# COEXPIX_connectors_schematics.net
KiCad netlist of a schematic drawn in Altium Designer
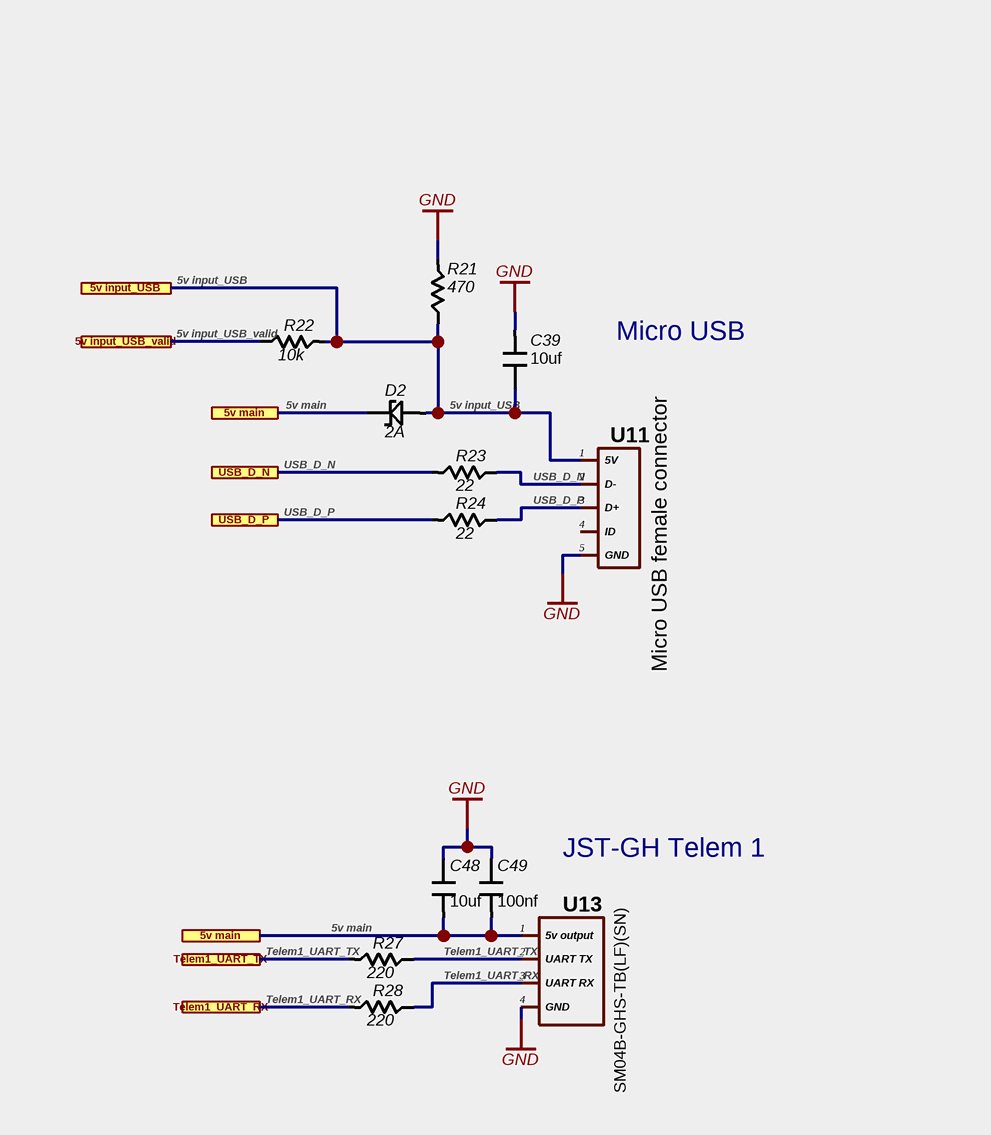
[diagram p0: COEXPIX connectors schematics.SchDoc, top left]
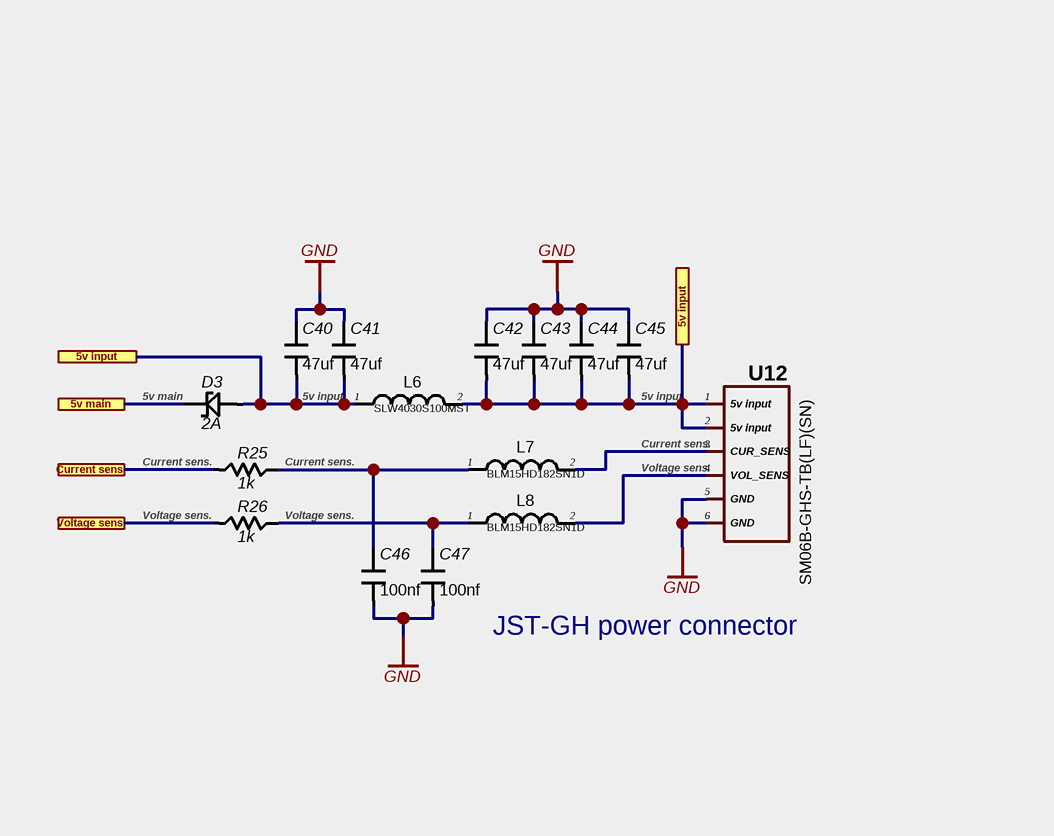
[diagram p1: COEXPIX connectors schematics.SchDoc, top right]
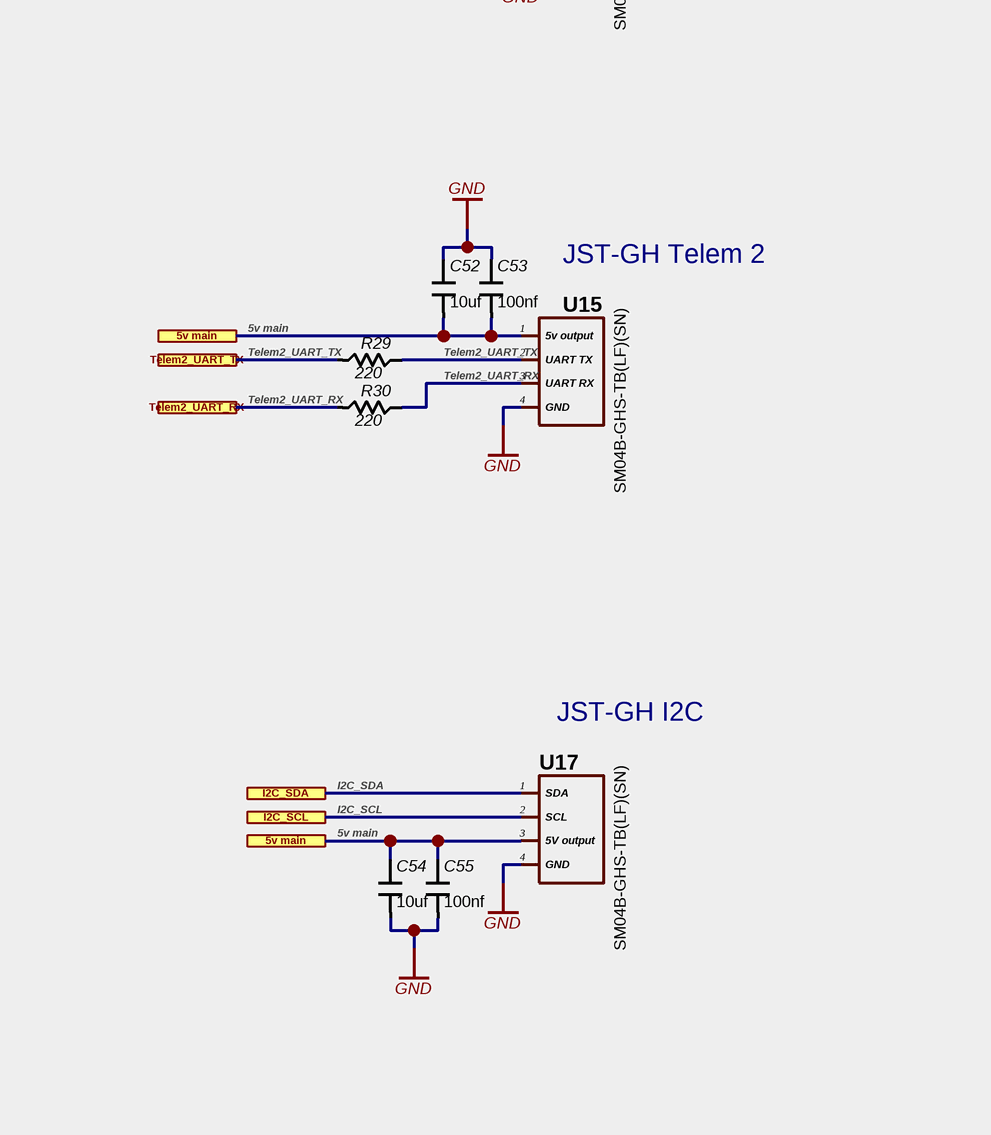
[diagram p2: COEXPIX connectors schematics.SchDoc, bottom left]
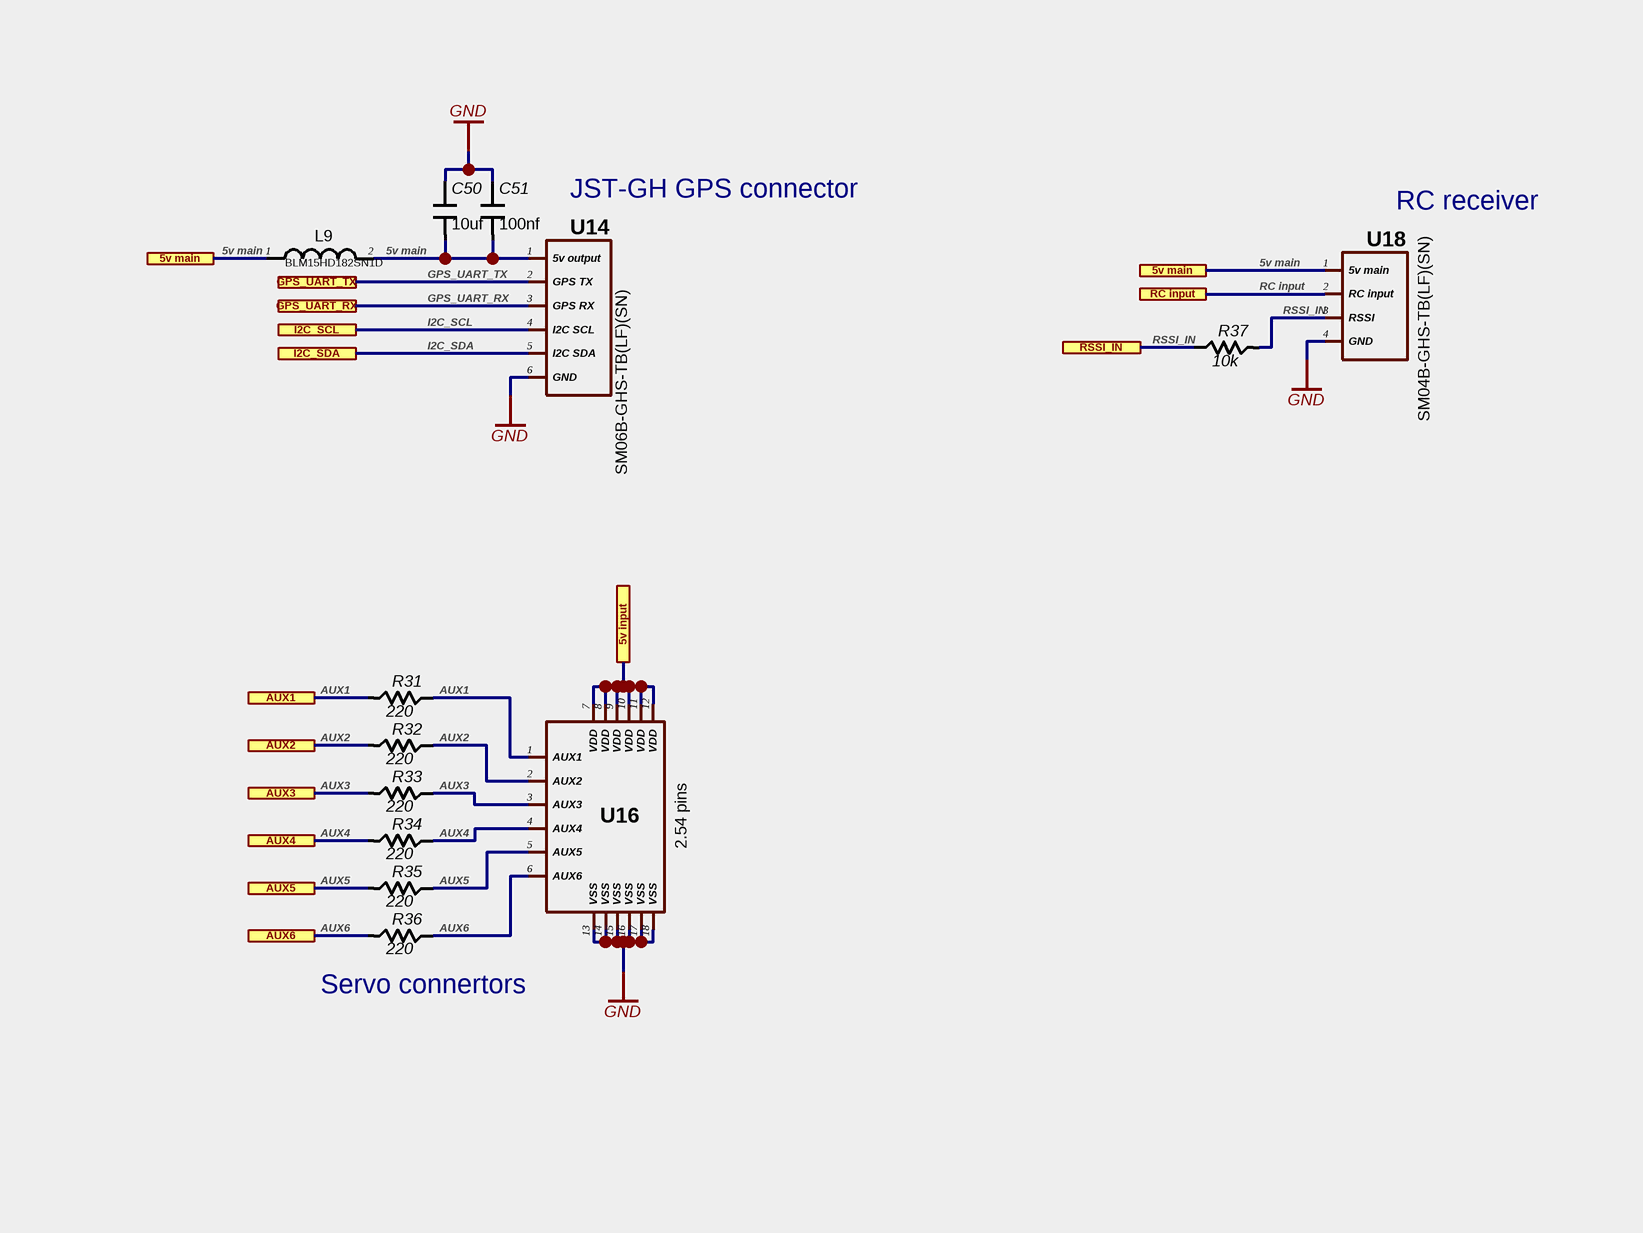
[diagram p3: COEXPIX connectors schematics.SchDoc, bottom right]

(export (version "E")
  (design (tool "Eeschema 10.0.6"))
  (components
    (comp (ref "C39")
      (value "10uf")
      (footprint "Capasitor 0402")
      (description "Multilayer Ceramic Capacitors MLCC - SMD/SMT 10uF 6.3V 0402")
      (fields (field (name "PART NUMBER") "JMK105CBJ106MV-F") (field (name "MANUFACTURER") "Taiyo Yuden"))
      (libsource (lib "Schematic symbols library") (part "Capacitor MLCC"))
    )
    (comp (ref "C40")
      (value "47uf")
      (footprint "Capasitor 0603")
      (description "Multilayer Ceramic Capacitors MLCC - SMD/SMT 47uF 6.3V 0603")
      (fields (field (name "PART NUMBER") "GRM188R60J476ME15D") (field (name "MANUFACTURER") "Murata"))
      (libsource (lib "Schematic symbols library") (part "Capacitor MLCC"))
    )
    (comp (ref "C41")
      (value "47uf")
      (footprint "Capasitor 0603")
      (description "Multilayer Ceramic Capacitors MLCC - SMD/SMT 47uF 6.3V 0603")
      (fields (field (name "PART NUMBER") "GRM188R60J476ME15D") (field (name "MANUFACTURER") "Murata"))
      (libsource (lib "Schematic symbols library") (part "Capacitor MLCC"))
    )
    (comp (ref "C42")
      (value "47uf")
      (footprint "Capasitor 0603")
      (description "Multilayer Ceramic Capacitors MLCC - SMD/SMT 47uF 6.3V 0603")
      (fields (field (name "PART NUMBER") "GRM188R60J476ME15D") (field (name "MANUFACTURER") "Murata"))
      (libsource (lib "Schematic symbols library") (part "Capacitor MLCC"))
    )
    (comp (ref "C43")
      (value "47uf")
      (footprint "Capasitor 0603")
      (description "Multilayer Ceramic Capacitors MLCC - SMD/SMT 47uF 6.3V 0603")
      (fields (field (name "PART NUMBER") "GRM188R60J476ME15D") (field (name "MANUFACTURER") "Murata"))
      (libsource (lib "Schematic symbols library") (part "Capacitor MLCC"))
    )
    (comp (ref "C44")
      (value "47uf")
      (footprint "Capasitor 0603")
      (description "Multilayer Ceramic Capacitors MLCC - SMD/SMT 47uF 6.3V 0603")
      (fields (field (name "PART NUMBER") "GRM188R60J476ME15D") (field (name "MANUFACTURER") "Murata"))
      (libsource (lib "Schematic symbols library") (part "Capacitor MLCC"))
    )
    (comp (ref "C45")
      (value "47uf")
      (footprint "Capasitor 0603")
      (description "Multilayer Ceramic Capacitors MLCC - SMD/SMT 47uF 6.3V 0603")
      (fields (field (name "PART NUMBER") "GRM188R60J476ME15D") (field (name "MANUFACTURER") "Murata"))
      (libsource (lib "Schematic symbols library") (part "Capacitor MLCC"))
    )
    (comp (ref "C46")
      (value "100nf")
      (footprint "Capasitor 0402")
      (description "Multilayer Ceramic Capacitors MLCC - SMD/SMT 100nF 16V 0402")
      (fields (field (name "PART NUMBER") "CC0402KRX7R7BB104") (field (name "MANUFACTURER") "YAGEO"))
      (libsource (lib "Schematic symbols library") (part "Capacitor MLCC"))
    )
    (comp (ref "C47")
      (value "100nf")
      (footprint "Capasitor 0402")
      (description "Multilayer Ceramic Capacitors MLCC - SMD/SMT 100nF 16V 0402")
      (fields (field (name "PART NUMBER") "CC0402KRX7R7BB104") (field (name "MANUFACTURER") "YAGEO"))
      (libsource (lib "Schematic symbols library") (part "Capacitor MLCC"))
    )
    (comp (ref "C48")
      (value "10uf")
      (footprint "Capasitor 0402")
      (description "Multilayer Ceramic Capacitors MLCC - SMD/SMT 10uF 6.3V 0402")
      (fields (field (name "PART NUMBER") "JMK105CBJ106MV-F") (field (name "MANUFACTURER") "Taiyo Yuden"))
      (libsource (lib "Schematic symbols library") (part "Capacitor MLCC"))
    )
    (comp (ref "C49")
      (value "100nf")
      (footprint "Capasitor 0402")
      (description "Multilayer Ceramic Capacitors MLCC - SMD/SMT 100nF 16V 0402")
      (fields (field (name "PART NUMBER") "CC0402KRX7R7BB104") (field (name "MANUFACTURER") "YAGEO"))
      (libsource (lib "Schematic symbols library") (part "Capacitor MLCC"))
    )
    (comp (ref "C50")
      (value "10uf")
      (footprint "Capasitor 0402")
      (description "Multilayer Ceramic Capacitors MLCC - SMD/SMT 10uF 6.3V 0402")
      (fields (field (name "PART NUMBER") "JMK105CBJ106MV-F") (field (name "MANUFACTURER") "Taiyo Yuden"))
      (libsource (lib "Schematic symbols library") (part "Capacitor MLCC"))
    )
    (comp (ref "C51")
      (value "100nf")
      (footprint "Capasitor 0402")
      (description "Multilayer Ceramic Capacitors MLCC - SMD/SMT 100nF 16V 0402")
      (fields (field (name "PART NUMBER") "CC0402KRX7R7BB104") (field (name "MANUFACTURER") "YAGEO"))
      (libsource (lib "Schematic symbols library") (part "Capacitor MLCC"))
    )
    (comp (ref "C52")
      (value "10uf")
      (footprint "Capasitor 0402")
      (description "Multilayer Ceramic Capacitors MLCC - SMD/SMT 10uF 6.3V 0402")
      (fields (field (name "PART NUMBER") "JMK105CBJ106MV-F") (field (name "MANUFACTURER") "Taiyo Yuden"))
      (libsource (lib "Schematic symbols library") (part "Capacitor MLCC"))
    )
    (comp (ref "C53")
      (value "100nf")
      (footprint "Capasitor 0402")
      (description "Multilayer Ceramic Capacitors MLCC - SMD/SMT 100nF 16V 0402")
      (fields (field (name "PART NUMBER") "CC0402KRX7R7BB104") (field (name "MANUFACTURER") "YAGEO"))
      (libsource (lib "Schematic symbols library") (part "Capacitor MLCC"))
    )
    (comp (ref "C54")
      (value "10uf")
      (footprint "Capasitor 0402")
      (description "Multilayer Ceramic Capacitors MLCC - SMD/SMT 10uF 6.3V 0402")
      (fields (field (name "PART NUMBER") "JMK105CBJ106MV-F") (field (name "MANUFACTURER") "Taiyo Yuden"))
      (libsource (lib "Schematic symbols library") (part "Capacitor MLCC"))
    )
    (comp (ref "C55")
      (value "100nf")
      (footprint "Capasitor 0402")
      (description "Multilayer Ceramic Capacitors MLCC - SMD/SMT 100nF 16V 0402")
      (fields (field (name "PART NUMBER") "CC0402KRX7R7BB104") (field (name "MANUFACTURER") "YAGEO"))
      (libsource (lib "Schematic symbols library") (part "Capacitor MLCC"))
    )
    (comp (ref "D2")
      (value "2A")
      (footprint "SOD-323F")
      (description "Schottky Barrier Diodes (SBD) SOD-323F")
      (fields (field (name "PART NUMBER") "SGP0230SD") (field (name "MANUFACTURER") "Suzhou Good-Ark Elec"))
      (libsource (lib "Schematic symbols library") (part "Schottky barrier diode"))
    )
    (comp (ref "D3")
      (value "2A")
      (footprint "SOD-323F")
      (description "Schottky Barrier Diodes (SBD) SOD-323F")
      (fields (field (name "PART NUMBER") "SGP0230SD") (field (name "MANUFACTURER") "Suzhou Good-Ark Elec"))
      (libsource (lib "Schematic symbols library") (part "Schottky barrier diode"))
    )
    (comp (ref "L6")
      (value "SLW4030S100MST")
      (footprint "Inductor 4030")
      (description "Power Inductors 10uH ±20% 1.5A SMD,4x4x3mm")
      (fields (field (name "MANUFACTURER") "Sunltech Tech"))
      (libsource (lib "Schematic symbols library") (part "FB / Inductor"))
    )
    (comp (ref "L7")
      (value "BLM15HD182SN1D")
      (footprint "Ferrite bead 0402")
      (description "Beads 0402")
      (fields (field (name "MANUFACTURER") "Murata Electronics"))
      (libsource (lib "Schematic symbols library") (part "FB / Inductor"))
    )
    (comp (ref "L8")
      (value "BLM15HD182SN1D")
      (footprint "Ferrite bead 0402")
      (description "Beads 0402")
      (fields (field (name "MANUFACTURER") "Murata Electronics"))
      (libsource (lib "Schematic symbols library") (part "FB / Inductor"))
    )
    (comp (ref "L9")
      (value "BLM15HD182SN1D")
      (footprint "Ferrite bead 0402")
      (description "Beads 0402")
      (fields (field (name "MANUFACTURER") "Murata Electronics"))
      (libsource (lib "Schematic symbols library") (part "FB / Inductor"))
    )
    (comp (ref "R21")
      (value "470")
      (footprint "Resistor 0402")
      (description "Chip Resistor - Surface Mount 470Ohms ±1% 1/16W 0402")
      (fields (field (name "PART NUMBER") "RC0402FR-07470RL") (field (name "MANUFACTURER") "YAGEO"))
      (libsource (lib "Schematic symbols library") (part "Resistor"))
    )
    (comp (ref "R22")
      (value "10k")
      (footprint "Resistor 0402")
      (description "Chip Resistor - Surface Mount 10KOhms ±1% 1/16W 0402")
      (fields (field (name "PART NUMBER") "RC0402FR-0710KL") (field (name "MANUFACTURER") "YAGEO"))
      (libsource (lib "Schematic symbols library") (part "Resistor"))
    )
    (comp (ref "R23")
      (value "22")
      (footprint "Resistor 0402")
      (description "Chip Resistor - Surface Mount 22Ohms ±1% 1/16W 0402")
      (fields (field (name "PART NUMBER") "RC0402FR-0722RL") (field (name "MANUFACTURER") "YAGEO"))
      (libsource (lib "Schematic symbols library") (part "Resistor"))
    )
    (comp (ref "R24")
      (value "22")
      (footprint "Resistor 0402")
      (description "Chip Resistor - Surface Mount 22Ohms ±1% 1/16W 0402")
      (fields (field (name "PART NUMBER") "RC0402FR-0722RL") (field (name "MANUFACTURER") "YAGEO"))
      (libsource (lib "Schematic symbols library") (part "Resistor"))
    )
    (comp (ref "R25")
      (value "1k")
      (footprint "Resistor 0402")
      (description "Chip Resistor - Surface Mount 1KOhms ±1% 1/16W 0402")
      (fields (field (name "PART NUMBER") "RC0402FR-071KL") (field (name "MANUFACTURER") "YAGEO"))
      (libsource (lib "Schematic symbols library") (part "Resistor"))
    )
    (comp (ref "R26")
      (value "1k")
      (footprint "Resistor 0402")
      (description "Chip Resistor - Surface Mount 1KOhms ±1% 1/16W 0402")
      (fields (field (name "PART NUMBER") "RC0402FR-071KL") (field (name "MANUFACTURER") "YAGEO"))
      (libsource (lib "Schematic symbols library") (part "Resistor"))
    )
    (comp (ref "R27")
      (value "220")
      (footprint "Resistor 0402")
      (description "Chip Resistor - Surface Mount 220Ohms ±1% 1/16W 040")
      (fields (field (name "PART NUMBER") "0402WGF2200TCE") (field (name "MANUFACTURER") "Uniroyal Elec"))
      (libsource (lib "Schematic symbols library") (part "Resistor"))
    )
    (comp (ref "R28")
      (value "220")
      (footprint "Resistor 0402")
      (description "Chip Resistor - Surface Mount 220Ohms ±1% 1/16W 040")
      (fields (field (name "PART NUMBER") "0402WGF2200TCE") (field (name "MANUFACTURER") "Uniroyal Elec"))
      (libsource (lib "Schematic symbols library") (part "Resistor"))
    )
    (comp (ref "R29")
      (value "220")
      (footprint "Resistor 0402")
      (description "Chip Resistor - Surface Mount 220Ohms ±1% 1/16W 040")
      (fields (field (name "PART NUMBER") "0402WGF2200TCE") (field (name "MANUFACTURER") "Uniroyal Elec"))
      (libsource (lib "Schematic symbols library") (part "Resistor"))
    )
    (comp (ref "R30")
      (value "220")
      (footprint "Resistor 0402")
      (description "Chip Resistor - Surface Mount 220Ohms ±1% 1/16W 040")
      (fields (field (name "PART NUMBER") "0402WGF2200TCE") (field (name "MANUFACTURER") "Uniroyal Elec"))
      (libsource (lib "Schematic symbols library") (part "Resistor"))
    )
    (comp (ref "R31")
      (value "220")
      (footprint "Resistor 0402")
      (description "Chip Resistor - Surface Mount 220Ohms ±1% 1/16W 040")
      (fields (field (name "PART NUMBER") "0402WGF2200TCE") (field (name "MANUFACTURER") "Uniroyal Elec"))
      (libsource (lib "Schematic symbols library") (part "Resistor"))
    )
    (comp (ref "R32")
      (value "220")
      (footprint "Resistor 0402")
      (description "Chip Resistor - Surface Mount 220Ohms ±1% 1/16W 040")
      (fields (field (name "PART NUMBER") "0402WGF2200TCE") (field (name "MANUFACTURER") "Uniroyal Elec"))
      (libsource (lib "Schematic symbols library") (part "Resistor"))
    )
    (comp (ref "R33")
      (value "220")
      (footprint "Resistor 0402")
      (description "Chip Resistor - Surface Mount 220Ohms ±1% 1/16W 040")
      (fields (field (name "PART NUMBER") "0402WGF2200TCE") (field (name "MANUFACTURER") "Uniroyal Elec"))
      (libsource (lib "Schematic symbols library") (part "Resistor"))
    )
    (comp (ref "R34")
      (value "220")
      (footprint "Resistor 0402")
      (description "Chip Resistor - Surface Mount 220Ohms ±1% 1/16W 040")
      (fields (field (name "PART NUMBER") "0402WGF2200TCE") (field (name "MANUFACTURER") "Uniroyal Elec"))
      (libsource (lib "Schematic symbols library") (part "Resistor"))
    )
    (comp (ref "R35")
      (value "220")
      (footprint "Resistor 0402")
      (description "Chip Resistor - Surface Mount 220Ohms ±1% 1/16W 040")
      (fields (field (name "PART NUMBER") "0402WGF2200TCE") (field (name "MANUFACTURER") "Uniroyal Elec"))
      (libsource (lib "Schematic symbols library") (part "Resistor"))
    )
    (comp (ref "R36")
      (value "220")
      (footprint "Resistor 0402")
      (description "Chip Resistor - Surface Mount 220Ohms ±1% 1/16W 040")
      (fields (field (name "PART NUMBER") "0402WGF2200TCE") (field (name "MANUFACTURER") "Uniroyal Elec"))
      (libsource (lib "Schematic symbols library") (part "Resistor"))
    )
    (comp (ref "R37")
      (value "10k")
      (footprint "Resistor 0402")
      (description "Chip Resistor - Surface Mount 10KOhms ±1% 1/16W 0402")
      (fields (field (name "PART NUMBER") "RC0402FR-0710KL") (field (name "MANUFACTURER") "YAGEO"))
      (libsource (lib "Schematic symbols library") (part "Resistor"))
    )
    (comp (ref "U11")
      (value "Micro USB female connector")
      (footprint "Micro USB")
      (libsource (lib "Schematic symbols library") (part "Micro USB"))
    )
    (comp (ref "U12")
      (value "SM06B-GHS-TB(LF)(SN)")
      (footprint "JST-GH 6 PIN")
      (description "Wire To Board / Wire To Wire Connector SMD")
      (fields (field (name "MANUFACTURER") "JST Sales America"))
      (libsource (lib "Schematic symbols library") (part "JST-GH 6"))
    )
    (comp (ref "U13")
      (value "SM04B-GHS-TB(LF)(SN)")
      (footprint "JST-GH 4 pin")
      (description "Wire To Board / Wire To Wire Connector socket P=1.25mm")
      (fields (field (name "MANUFACTURER") "JST Sales America"))
      (libsource (lib "Schematic symbols library") (part "JST-GH 4"))
    )
    (comp (ref "U14")
      (value "SM06B-GHS-TB(LF)(SN)")
      (footprint "JST-GH 6 PIN")
      (description "Wire To Board / Wire To Wire Connector SMD")
      (fields (field (name "MANUFACTURER") "JST Sales America"))
      (libsource (lib "Schematic symbols library") (part "JST-GH 6"))
    )
    (comp (ref "U15")
      (value "SM04B-GHS-TB(LF)(SN)")
      (footprint "JST-GH 4 pin")
      (description "Wire To Board / Wire To Wire Connector socket P=1.25mm")
      (fields (field (name "MANUFACTURER") "JST Sales America"))
      (libsource (lib "Schematic symbols library") (part "JST-GH 4"))
    )
    (comp (ref "U16")
      (value "2.54 pins")
      (footprint "3x6 PX4 servo array")
      (fields (field (name "PART NUMBER") "2.54 pins array"))
      (libsource (lib "Schematic symbols library") (part "3x6 dupont pins"))
    )
    (comp (ref "U17")
      (value "SM04B-GHS-TB(LF)(SN)")
      (footprint "JST-GH 4 pin")
      (description "Wire To Board / Wire To Wire Connector socket P=1.25mm")
      (fields (field (name "MANUFACTURER") "JST Sales America"))
      (libsource (lib "Schematic symbols library") (part "JST-GH 4"))
    )
    (comp (ref "U18")
      (value "SM04B-GHS-TB(LF)(SN)")
      (footprint "JST-GH 4 pin")
      (description "Wire To Board / Wire To Wire Connector socket P=1.25mm")
      (fields (field (name "MANUFACTURER") "JST Sales America"))
      (libsource (lib "Schematic symbols library") (part "JST-GH 4"))
    )
  )
  (nets
    (net (code "1") (name "/5v input") (class "Default")
      (node (ref "C40") (pin "2") (pinfunction "2_2") (pintype "passive"))
      (node (ref "C41") (pin "2") (pinfunction "2_2") (pintype "passive"))
      (node (ref "C42") (pin "2") (pinfunction "2_2") (pintype "passive"))
      (node (ref "C43") (pin "2") (pinfunction "2_2") (pintype "passive"))
      (node (ref "C44") (pin "2") (pinfunction "2_2") (pintype "passive"))
      (node (ref "C45") (pin "2") (pinfunction "2_2") (pintype "passive"))
      (node (ref "D3") (pin "2") (pinfunction "2_2") (pintype "passive"))
      (node (ref "L6") (pin "1") (pintype "power_in"))
      (node (ref "L6") (pin "2") (pintype "power_in"))
      (node (ref "U12") (pin "1") (pinfunction "5v_output_1") (pintype "power_in"))
      (node (ref "U12") (pin "2") (pinfunction "GPS_TX_2") (pintype "power_in"))
      (node (ref "U16") (pin "10") (pinfunction "VDD_10") (pintype "power_in"))
      (node (ref "U16") (pin "11") (pinfunction "VDD_11") (pintype "power_in"))
      (node (ref "U16") (pin "12") (pinfunction "VDD_12") (pintype "power_in"))
      (node (ref "U16") (pin "7") (pinfunction "VDD_7") (pintype "power_in"))
      (node (ref "U16") (pin "8") (pinfunction "VDD_8") (pintype "power_in"))
      (node (ref "U16") (pin "9") (pinfunction "VDD_9") (pintype "power_in"))
    )
    (net (code "2") (name "/5v input_USB") (class "Default")
      (node (ref "C39") (pin "1") (pinfunction "1_1") (pintype "passive"))
      (node (ref "D2") (pin "2") (pinfunction "2_2") (pintype "passive"))
      (node (ref "R21") (pin "1") (pinfunction "1_1") (pintype "passive"))
      (node (ref "R22") (pin "2") (pinfunction "2_2") (pintype "passive"))
      (node (ref "U11") (pin "1") (pinfunction "5V_1") (pintype "power_in"))
    )
    (net (code "3") (name "/5v input_USB_valid") (class "Default")
      (node (ref "R22") (pin "1") (pinfunction "1_1") (pintype "passive"))
    )
    (net (code "4") (name "/5v main") (class "Default")
      (node (ref "C48") (pin "2") (pinfunction "2_2") (pintype "passive"))
      (node (ref "C49") (pin "2") (pinfunction "2_2") (pintype "passive"))
      (node (ref "C50") (pin "2") (pinfunction "2_2") (pintype "passive"))
      (node (ref "C51") (pin "2") (pinfunction "2_2") (pintype "passive"))
      (node (ref "C52") (pin "2") (pinfunction "2_2") (pintype "passive"))
      (node (ref "C53") (pin "2") (pinfunction "2_2") (pintype "passive"))
      (node (ref "C54") (pin "1") (pinfunction "1_1") (pintype "passive"))
      (node (ref "C55") (pin "1") (pinfunction "1_1") (pintype "passive"))
      (node (ref "D2") (pin "1") (pinfunction "1_1") (pintype "passive"))
      (node (ref "D3") (pin "1") (pinfunction "1_1") (pintype "passive"))
      (node (ref "L9") (pin "1") (pintype "power_in"))
      (node (ref "L9") (pin "2") (pintype "power_in"))
      (node (ref "U13") (pin "1") (pinfunction "5v_output_1") (pintype "power_in"))
      (node (ref "U14") (pin "1") (pinfunction "5v_output_1") (pintype "power_in"))
      (node (ref "U15") (pin "1") (pinfunction "5v_output_1") (pintype "power_in"))
      (node (ref "U17") (pin "3") (pinfunction "UART_RX_3") (pintype "power_in"))
      (node (ref "U18") (pin "1") (pinfunction "5v_output_1") (pintype "power_in"))
    )
    (net (code "5") (name "/AUX1") (class "Default")
      (node (ref "R31") (pin "1") (pinfunction "1_1") (pintype "passive"))
      (node (ref "R31") (pin "2") (pinfunction "2_2") (pintype "passive"))
      (node (ref "U16") (pin "1") (pinfunction "AUX1_1") (pintype "power_in"))
    )
    (net (code "6") (name "/AUX2") (class "Default")
      (node (ref "R32") (pin "1") (pinfunction "1_1") (pintype "passive"))
      (node (ref "R32") (pin "2") (pinfunction "2_2") (pintype "passive"))
      (node (ref "U16") (pin "2") (pinfunction "AUX2_2") (pintype "power_in"))
    )
    (net (code "7") (name "/AUX3") (class "Default")
      (node (ref "R33") (pin "1") (pinfunction "1_1") (pintype "passive"))
      (node (ref "R33") (pin "2") (pinfunction "2_2") (pintype "passive"))
      (node (ref "U16") (pin "3") (pinfunction "AUX3_3") (pintype "power_in"))
    )
    (net (code "8") (name "/AUX4") (class "Default")
      (node (ref "R34") (pin "1") (pinfunction "1_1") (pintype "passive"))
      (node (ref "R34") (pin "2") (pinfunction "2_2") (pintype "passive"))
      (node (ref "U16") (pin "4") (pinfunction "AUX4_4") (pintype "power_in"))
    )
    (net (code "9") (name "/AUX5") (class "Default")
      (node (ref "R35") (pin "1") (pinfunction "1_1") (pintype "passive"))
      (node (ref "R35") (pin "2") (pinfunction "2_2") (pintype "passive"))
      (node (ref "U16") (pin "5") (pinfunction "AUX5_5") (pintype "power_in"))
    )
    (net (code "10") (name "/AUX6") (class "Default")
      (node (ref "R36") (pin "1") (pinfunction "1_1") (pintype "passive"))
      (node (ref "R36") (pin "2") (pinfunction "2_2") (pintype "passive"))
      (node (ref "U16") (pin "6") (pinfunction "AUX6_6") (pintype "power_in"))
    )
    (net (code "11") (name "/Current sens.") (class "Default")
      (node (ref "C46") (pin "1") (pinfunction "1_1") (pintype "passive"))
      (node (ref "L7") (pin "1") (pintype "power_in"))
      (node (ref "L7") (pin "2") (pintype "power_in"))
      (node (ref "R25") (pin "1") (pinfunction "1_1") (pintype "passive"))
      (node (ref "R25") (pin "2") (pinfunction "2_2") (pintype "passive"))
      (node (ref "U12") (pin "3") (pinfunction "GPS_RX_3") (pintype "power_in"))
    )
    (net (code "12") (name "/GPS_UART_RX") (class "Default")
      (node (ref "U14") (pin "3") (pinfunction "GPS_RX_3") (pintype "power_in"))
    )
    (net (code "13") (name "/GPS_UART_TX") (class "Default")
      (node (ref "U14") (pin "2") (pinfunction "GPS_TX_2") (pintype "power_in"))
    )
    (net (code "14") (name "/I2C_SCL") (class "Default")
      (node (ref "U14") (pin "4") (pinfunction "I2C_SCL_4") (pintype "power_in"))
      (node (ref "U17") (pin "2") (pinfunction "UART_TX_2") (pintype "power_in"))
    )
    (net (code "15") (name "/I2C_SDA") (class "Default")
      (node (ref "U14") (pin "5") (pinfunction "I2C_SDA_5") (pintype "power_in"))
      (node (ref "U17") (pin "1") (pinfunction "5v_output_1") (pintype "power_in"))
    )
    (net (code "16") (name "/RC input") (class "Default")
      (node (ref "U18") (pin "2") (pinfunction "UART_TX_2") (pintype "power_in"))
    )
    (net (code "17") (name "/RSSI_IN") (class "Default")
      (node (ref "R37") (pin "1") (pinfunction "1_1") (pintype "passive"))
      (node (ref "R37") (pin "2") (pinfunction "2_2") (pintype "passive"))
      (node (ref "U18") (pin "3") (pinfunction "UART_RX_3") (pintype "power_in"))
    )
    (net (code "18") (name "/Telem1_UART_RX") (class "Default")
      (node (ref "R28") (pin "1") (pinfunction "1_1") (pintype "passive"))
      (node (ref "R28") (pin "2") (pinfunction "2_2") (pintype "passive"))
      (node (ref "U13") (pin "3") (pinfunction "UART_RX_3") (pintype "power_in"))
    )
    (net (code "19") (name "/Telem1_UART_TX") (class "Default")
      (node (ref "R27") (pin "1") (pinfunction "1_1") (pintype "passive"))
      (node (ref "R27") (pin "2") (pinfunction "2_2") (pintype "passive"))
      (node (ref "U13") (pin "2") (pinfunction "UART_TX_2") (pintype "power_in"))
    )
    (net (code "20") (name "/Telem2_UART_RX") (class "Default")
      (node (ref "R30") (pin "1") (pinfunction "1_1") (pintype "passive"))
      (node (ref "R30") (pin "2") (pinfunction "2_2") (pintype "passive"))
      (node (ref "U15") (pin "3") (pinfunction "UART_RX_3") (pintype "power_in"))
    )
    (net (code "21") (name "/Telem2_UART_TX") (class "Default")
      (node (ref "R29") (pin "1") (pinfunction "1_1") (pintype "passive"))
      (node (ref "R29") (pin "2") (pinfunction "2_2") (pintype "passive"))
      (node (ref "U15") (pin "2") (pinfunction "UART_TX_2") (pintype "power_in"))
    )
    (net (code "22") (name "/USB_D_N") (class "Default")
      (node (ref "R23") (pin "1") (pinfunction "1_1") (pintype "passive"))
      (node (ref "R23") (pin "2") (pinfunction "2_2") (pintype "passive"))
      (node (ref "U11") (pin "2") (pinfunction "D-_2") (pintype "power_in"))
    )
    (net (code "23") (name "/USB_D_P") (class "Default")
      (node (ref "R24") (pin "1") (pinfunction "1_1") (pintype "passive"))
      (node (ref "R24") (pin "2") (pinfunction "2_2") (pintype "passive"))
      (node (ref "U11") (pin "3") (pinfunction "D+_3") (pintype "power_in"))
    )
    (net (code "24") (name "/Voltage sens.") (class "Default")
      (node (ref "C47") (pin "1") (pinfunction "1_1") (pintype "passive"))
      (node (ref "L8") (pin "1") (pintype "power_in"))
      (node (ref "L8") (pin "2") (pintype "power_in"))
      (node (ref "R26") (pin "1") (pinfunction "1_1") (pintype "passive"))
      (node (ref "R26") (pin "2") (pinfunction "2_2") (pintype "passive"))
      (node (ref "U12") (pin "4") (pinfunction "I2C_SCL_4") (pintype "power_in"))
    )
    (net (code "25") (name "GND") (class "Default")
      (node (ref "C39") (pin "2") (pinfunction "2_2") (pintype "passive"))
      (node (ref "C40") (pin "1") (pinfunction "1_1") (pintype "passive"))
      (node (ref "C41") (pin "1") (pinfunction "1_1") (pintype "passive"))
      (node (ref "C42") (pin "1") (pinfunction "1_1") (pintype "passive"))
      (node (ref "C43") (pin "1") (pinfunction "1_1") (pintype "passive"))
      (node (ref "C44") (pin "1") (pinfunction "1_1") (pintype "passive"))
      (node (ref "C45") (pin "1") (pinfunction "1_1") (pintype "passive"))
      (node (ref "C46") (pin "2") (pinfunction "2_2") (pintype "passive"))
      (node (ref "C47") (pin "2") (pinfunction "2_2") (pintype "passive"))
      (node (ref "C48") (pin "1") (pinfunction "1_1") (pintype "passive"))
      (node (ref "C49") (pin "1") (pinfunction "1_1") (pintype "passive"))
      (node (ref "C50") (pin "1") (pinfunction "1_1") (pintype "passive"))
      (node (ref "C51") (pin "1") (pinfunction "1_1") (pintype "passive"))
      (node (ref "C52") (pin "1") (pinfunction "1_1") (pintype "passive"))
      (node (ref "C53") (pin "1") (pinfunction "1_1") (pintype "passive"))
      (node (ref "C54") (pin "2") (pinfunction "2_2") (pintype "passive"))
      (node (ref "C55") (pin "2") (pinfunction "2_2") (pintype "passive"))
      (node (ref "R21") (pin "2") (pinfunction "2_2") (pintype "passive"))
      (node (ref "U11") (pin "5") (pinfunction "GND_5") (pintype "power_in"))
      (node (ref "U12") (pin "5") (pinfunction "I2C_SDA_5") (pintype "power_in"))
      (node (ref "U12") (pin "6") (pinfunction "GND_6") (pintype "power_in"))
      (node (ref "U13") (pin "4") (pinfunction "GND_4") (pintype "power_in"))
      (node (ref "U14") (pin "6") (pinfunction "GND_6") (pintype "power_in"))
      (node (ref "U15") (pin "4") (pinfunction "GND_4") (pintype "power_in"))
      (node (ref "U16") (pin "13") (pinfunction "VSS_13") (pintype "power_in"))
      (node (ref "U16") (pin "14") (pinfunction "VSS_14") (pintype "power_in"))
      (node (ref "U16") (pin "15") (pinfunction "VSS_15") (pintype "power_in"))
      (node (ref "U16") (pin "16") (pinfunction "VSS_16") (pintype "power_in"))
      (node (ref "U16") (pin "17") (pinfunction "VSS_17") (pintype "power_in"))
      (node (ref "U16") (pin "18") (pinfunction "VSS_18") (pintype "power_in"))
      (node (ref "U17") (pin "4") (pinfunction "GND_4") (pintype "power_in"))
      (node (ref "U18") (pin "4") (pinfunction "GND_4") (pintype "power_in"))
    )
    (net (code "26") (name "unconnected-(U11-ID-Pad4)") (class "Default")
      (node (ref "U11") (pin "4") (pinfunction "ID_4") (pintype "power_in"))
    )
  )
)
